# Grove_-_Luminance_Sensor_v1_0.net
KiCad netlist of a schematic drawn in EAGLE
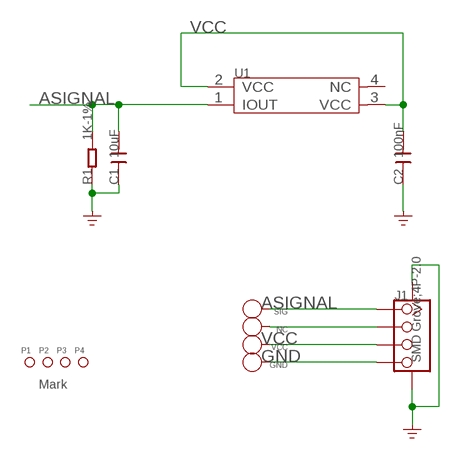
[diagram p0: schematic, sheet 1]

(export (version "E")
  (design (tool "Eeschema 10.0.6"))
  (components
    (comp (ref "C1")
      (value "10uF")
      (footprint "eagle-import:C0603")
      (libsource (lib "eagle-import") (part "C-0603"))
    )
    (comp (ref "C2")
      (value "100nF")
      (footprint "eagle-import:C0603")
      (libsource (lib "eagle-import") (part "C-0603"))
    )
    (comp (ref "GND")
      (value "PAD-TEST-POINT'4545'")
      (footprint "eagle-import:TP_4545")
      (fields (field (name "PARTNO") "DNP"))
      (libsource (lib "eagle-import") (part "PAD-TEST-POINT'4545'"))
    )
    (comp (ref "J1")
      (value "SMD Grove;4P-2.0")
      (footprint "eagle-import:4P-SMD-2.0")
      (libsource (lib "eagle-import") (part "TWIG-4P-2.0-SMD-FEMALE-REINFORCE'DD'"))
    )
    (comp (ref "NC")
      (value "PAD-TEST-POINT'4545'")
      (footprint "eagle-import:TP_4545")
      (fields (field (name "PARTNO") "DNP"))
      (libsource (lib "eagle-import") (part "PAD-TEST-POINT'4545'"))
    )
    (comp (ref "P1")
      (value "PAD-MARK")
      (footprint "eagle-import:ROUND-MARK-1.0")
      (fields (field (name "PARTNO") "DNP"))
      (libsource (lib "eagle-import") (part "PAD-MARK"))
    )
    (comp (ref "P2")
      (value "PAD-MARK")
      (footprint "eagle-import:ROUND-MARK-1.0")
      (fields (field (name "PARTNO") "DNP"))
      (libsource (lib "eagle-import") (part "PAD-MARK"))
    )
    (comp (ref "P3")
      (value "PAD-MARK")
      (footprint "eagle-import:ROUND-MARK-1.0")
      (fields (field (name "PARTNO") "DNP"))
      (libsource (lib "eagle-import") (part "PAD-MARK"))
    )
    (comp (ref "P4")
      (value "PAD-MARK")
      (footprint "eagle-import:ROUND-MARK-1.0")
      (fields (field (name "PARTNO") "DNP"))
      (libsource (lib "eagle-import") (part "PAD-MARK"))
    )
    (comp (ref "R1")
      (value "1K-1%")
      (footprint "eagle-import:R0603")
      (libsource (lib "eagle-import") (part "R-0603"))
    )
    (comp (ref "SIG")
      (value "PAD-TEST-POINT'4545'")
      (footprint "eagle-import:TP_4545")
      (fields (field (name "PARTNO") "DNP"))
      (libsource (lib "eagle-import") (part "PAD-TEST-POINT'4545'"))
    )
    (comp (ref "U1")
      (value "SENSOR-APDS-9002")
      (footprint "eagle-import:4P-SMD-2X1.25X0.8H")
      (libsource (lib "eagle-import") (part "SENSOR-APDS-9002"))
    )
    (comp (ref "VCC")
      (value "PAD-TEST-POINT'4545'")
      (footprint "eagle-import:TP_4545")
      (fields (field (name "PARTNO") "DNP"))
      (libsource (lib "eagle-import") (part "PAD-TEST-POINT'4545'"))
    )
  )
  (nets
    (net (code "1") (name "/ASIGNAL") (class "Default")
      (node (ref "C1") (pin "2") (pinfunction "2_2") (pintype "passive"))
      (node (ref "J1") (pin "1") (pinfunction "1_1") (pintype "bidirectional"))
      (node (ref "R1") (pin "2") (pinfunction "2_2") (pintype "passive"))
      (node (ref "SIG") (pin "T") (pinfunction "T_T") (pintype "bidirectional"))
      (node (ref "U1") (pin "1") (pinfunction "IOUT_1") (pintype "bidirectional"))
    )
    (net (code "2") (name "/VCC") (class "Default")
      (node (ref "C2") (pin "2") (pinfunction "2_2") (pintype "passive"))
      (node (ref "J1") (pin "3") (pinfunction "3_3") (pintype "bidirectional"))
      (node (ref "U1") (pin "2") (pinfunction "VCC_2") (pintype "bidirectional"))
      (node (ref "U1") (pin "3") (pinfunction "VCC_3") (pintype "bidirectional"))
      (node (ref "VCC") (pin "T") (pinfunction "T_T") (pintype "bidirectional"))
    )
    (net (code "3") (name "GND_POWER") (class "Default")
      (node (ref "C1") (pin "1") (pinfunction "1_1") (pintype "passive"))
      (node (ref "C2") (pin "1") (pinfunction "1_1") (pintype "passive"))
      (node (ref "GND") (pin "T") (pinfunction "T_T") (pintype "bidirectional"))
      (node (ref "J1") (pin "4") (pinfunction "4_4") (pintype "bidirectional"))
      (node (ref "J1") (pin "SS1") (pinfunction "SS1_SS1") (pintype "bidirectional"))
      (node (ref "J1") (pin "SS2") (pinfunction "SS2_SS2") (pintype "bidirectional"))
      (node (ref "R1") (pin "1") (pinfunction "1_1") (pintype "passive"))
    )
    (net (code "4") (name "Net-(J1-Pad2)") (class "Default")
      (node (ref "J1") (pin "2") (pinfunction "2_2") (pintype "bidirectional"))
      (node (ref "NC") (pin "T") (pinfunction "T_T") (pintype "bidirectional"))
    )
    (net (code "5") (name "unconnected-(U1-NC-Pad4)") (class "Default")
      (node (ref "U1") (pin "4") (pinfunction "NC_4") (pintype "bidirectional"))
    )
  )
)
